# Zerocopter.net
KiCad netlist of a schematic drawn in EAGLE
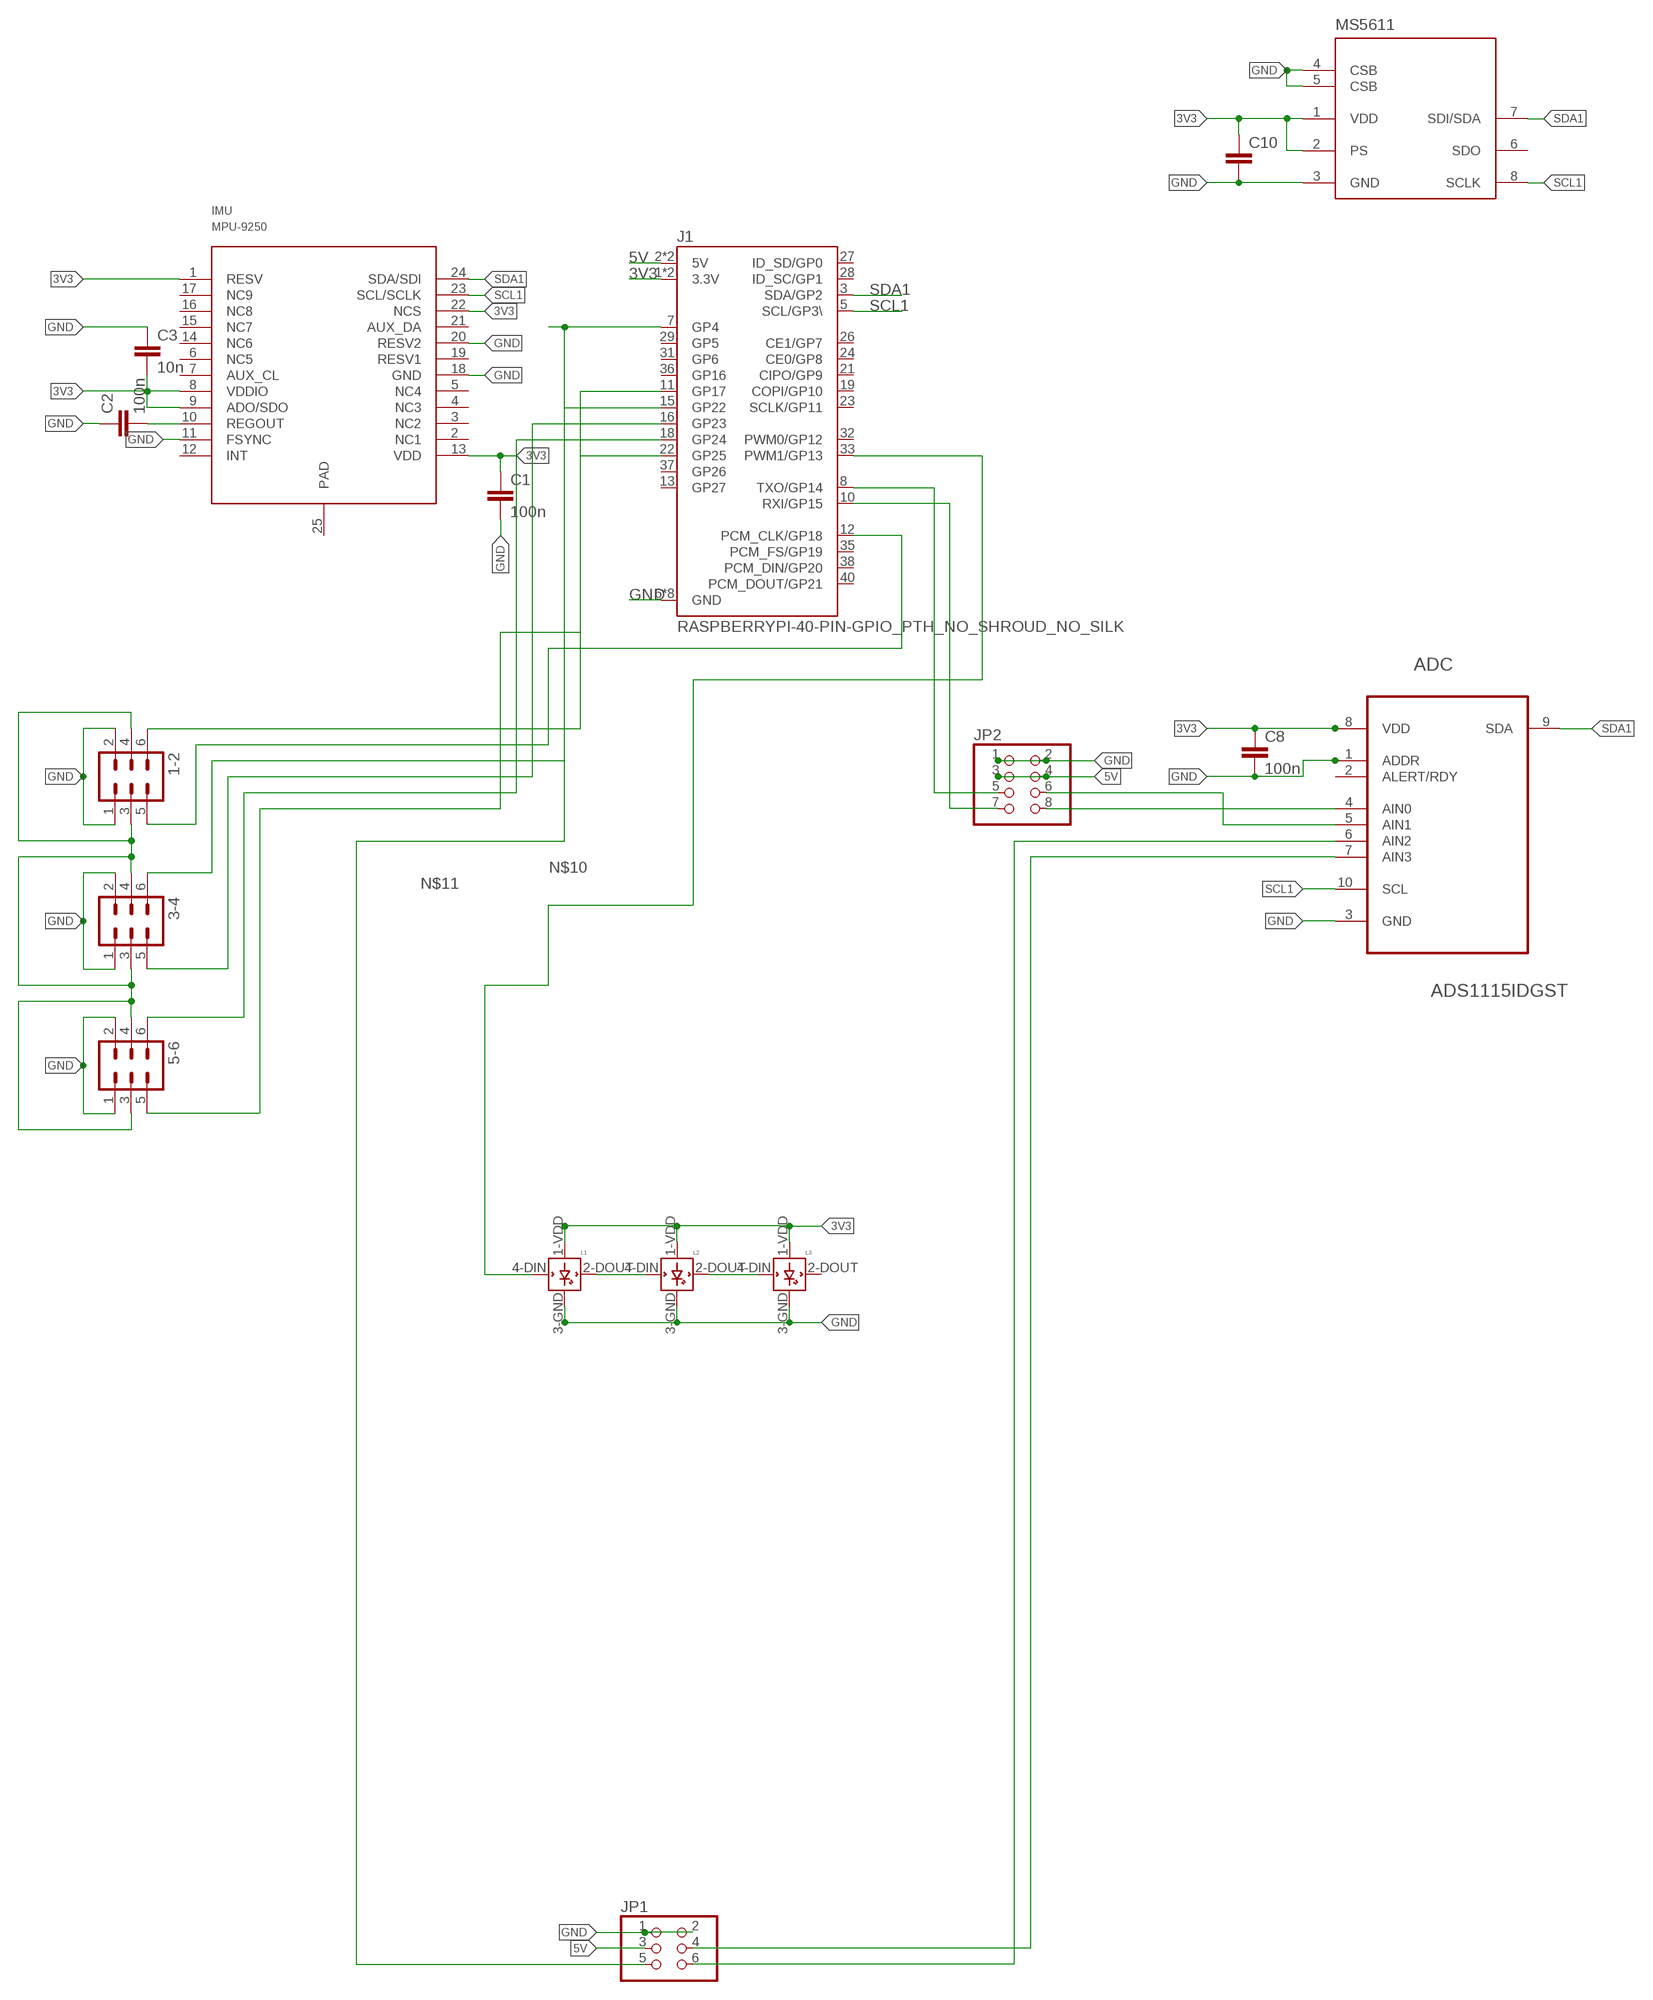
[diagram p0: schematic, sheet 1]

(export (version "E")
  (design (tool "Eeschema 10.0.6"))
  (components
    (comp (ref "1-2")
      (value "MA03-2")
      (footprint "eagle-import:MA03-2")
      (libsource (lib "eagle-import") (part "MA03-2"))
    )
    (comp (ref "3-4")
      (value "MA03-2")
      (footprint "eagle-import:MA03-2")
      (libsource (lib "eagle-import") (part "MA03-2"))
    )
    (comp (ref "5-6")
      (value "MA03-2")
      (footprint "eagle-import:MA03-2")
      (libsource (lib "eagle-import") (part "MA03-2"))
    )
    (comp (ref "ADC")
      (value "ADS1115IDGST")
      (footprint "eagle-import:SOP50P490X110-10N")
      (libsource (lib "eagle-import") (part "ADS1115IDGST"))
    )
    (comp (ref "C1")
      (value "100n")
      (footprint "eagle-import:C0603")
      (libsource (lib "eagle-import") (part "C-EUC0603"))
    )
    (comp (ref "C2")
      (value "100n")
      (footprint "eagle-import:C0603")
      (libsource (lib "eagle-import") (part "C-EUC0603"))
    )
    (comp (ref "C3")
      (value "10n")
      (footprint "eagle-import:C0603")
      (libsource (lib "eagle-import") (part "C-EUC0603"))
    )
    (comp (ref "C8")
      (value "100n")
      (footprint "eagle-import:C0603")
      (libsource (lib "eagle-import") (part "C-EUC0603"))
    )
    (comp (ref "C10")
      (value "C-EUC0603")
      (footprint "eagle-import:C0603")
      (libsource (lib "eagle-import") (part "C-EUC0603"))
    )
    (comp (ref "IMU")
      (value "MPU-9250")
      (footprint "eagle-import:LEAD-QFN24")
      (libsource (lib "eagle-import") (part "MPU-9250"))
    )
    (comp (ref "J1")
      (value "RASPBERRYPI-40-PIN-GPIO_PTH_NO_SHROUD_NO_SILK")
      (footprint "eagle-import:2X20_NOSILK")
      (libsource (lib "eagle-import") (part "RASPBERRYPI-40-PIN-GPIO_PTH_NO_SHROUD_NO_SILK"))
    )
    (comp (ref "JP1")
      (value "PINHD-2X3")
      (footprint "eagle-import:2X03")
      (libsource (lib "eagle-import") (part "PINHD-2X3"))
    )
    (comp (ref "JP2")
      (value "PINHD-2X4")
      (footprint "eagle-import:2X04")
      (libsource (lib "eagle-import") (part "PINHD-2X4"))
    )
    (comp (ref "L1")
      (value "WS2812B")
      (footprint "eagle-import:WS2812B")
      (libsource (lib "eagle-import") (part "WS2812B"))
    )
    (comp (ref "L2")
      (value "WS2812B")
      (footprint "eagle-import:WS2812B")
      (libsource (lib "eagle-import") (part "WS2812B"))
    )
    (comp (ref "L3")
      (value "WS2812B")
      (footprint "eagle-import:WS2812B")
      (libsource (lib "eagle-import") (part "WS2812B"))
    )
    (comp (ref "MS5611")
      (value "MS5611-01BA03")
      (footprint "eagle-import:SON125P300X500X100-8N")
      (libsource (lib "eagle-import") (part "MS5611-01BA03"))
    )
  )
  (nets
    (net (code "1") (name "/N$10") (class "Default")
      (node (ref "J1") (pin "33") (pinfunction "PWM1/GP13_33") (pintype "bidirectional"))
      (node (ref "L1") (pin "4-DIN") (pinfunction "DIN_4-DIN") (pintype "input"))
    )
    (net (code "2") (name "/N$11") (class "Default")
      (node (ref "J1") (pin "7") (pinfunction "GP4_7") (pintype "bidirectional"))
      (node (ref "JP1") (pin "5") (pinfunction "5_5") (pintype "passive"))
    )
    (net (code "3") (name "3V3") (class "Default")
      (node (ref "ADC") (pin "8") (pinfunction "VDD_8") (pintype "power_in"))
      (node (ref "C1") (pin "1") (pinfunction "1_1") (pintype "passive"))
      (node (ref "C10") (pin "1") (pinfunction "1_1") (pintype "passive"))
      (node (ref "C3") (pin "2") (pinfunction "2_2") (pintype "passive"))
      (node (ref "C8") (pin "1") (pinfunction "1_1") (pintype "passive"))
      (node (ref "IMU") (pin "1") (pinfunction "RESV_1") (pintype "bidirectional"))
      (node (ref "IMU") (pin "13") (pinfunction "VDD_13") (pintype "bidirectional"))
      (node (ref "IMU") (pin "22") (pinfunction "NCS_22") (pintype "bidirectional"))
      (node (ref "IMU") (pin "8") (pinfunction "VDDIO_8") (pintype "bidirectional"))
      (node (ref "IMU") (pin "9") (pinfunction "ADO/SDO_9") (pintype "bidirectional"))
      (node (ref "J1") (pin "1") (pinfunction "3.3V_1") (pintype "power_in"))
      (node (ref "J1") (pin "17") (pinfunction "3.3V_17") (pintype "power_in"))
      (node (ref "L1") (pin "1-VDD") (pinfunction "VDD_1-VDD") (pintype "bidirectional"))
      (node (ref "L2") (pin "1-VDD") (pinfunction "VDD_1-VDD") (pintype "bidirectional"))
      (node (ref "L3") (pin "1-VDD") (pinfunction "VDD_1-VDD") (pintype "bidirectional"))
      (node (ref "MS5611") (pin "1") (pinfunction "VDD_1") (pintype "power_in"))
      (node (ref "MS5611") (pin "2") (pinfunction "PS_2") (pintype "input"))
    )
    (net (code "4") (name "5V") (class "Default")
      (node (ref "J1") (pin "2") (pinfunction "5V_2") (pintype "power_in"))
      (node (ref "J1") (pin "4") (pinfunction "5V_4") (pintype "power_in"))
      (node (ref "JP1") (pin "3") (pinfunction "3_3") (pintype "passive"))
      (node (ref "JP2") (pin "3") (pinfunction "3_3") (pintype "passive"))
      (node (ref "JP2") (pin "4") (pinfunction "4_4") (pintype "passive"))
    )
    (net (code "5") (name "GND") (class "Default")
      (node (ref "1-2") (pin "1") (pinfunction "1_1") (pintype "passive"))
      (node (ref "1-2") (pin "2") (pinfunction "2_2") (pintype "passive"))
      (node (ref "3-4") (pin "1") (pinfunction "1_1") (pintype "passive"))
      (node (ref "3-4") (pin "2") (pinfunction "2_2") (pintype "passive"))
      (node (ref "5-6") (pin "1") (pinfunction "1_1") (pintype "passive"))
      (node (ref "5-6") (pin "2") (pinfunction "2_2") (pintype "passive"))
      (node (ref "ADC") (pin "1") (pinfunction "ADDR_1") (pintype "input"))
      (node (ref "ADC") (pin "3") (pinfunction "GND_3") (pintype "passive"))
      (node (ref "C1") (pin "2") (pinfunction "2_2") (pintype "passive"))
      (node (ref "C10") (pin "2") (pinfunction "2_2") (pintype "passive"))
      (node (ref "C2") (pin "1") (pinfunction "1_1") (pintype "passive"))
      (node (ref "C3") (pin "1") (pinfunction "1_1") (pintype "passive"))
      (node (ref "C8") (pin "2") (pinfunction "2_2") (pintype "passive"))
      (node (ref "IMU") (pin "11") (pinfunction "FSYNC_11") (pintype "bidirectional"))
      (node (ref "IMU") (pin "18") (pinfunction "GND_18") (pintype "bidirectional"))
      (node (ref "IMU") (pin "20") (pinfunction "RESV2_20") (pintype "bidirectional"))
      (node (ref "J1") (pin "14") (pinfunction "GND_14") (pintype "power_in"))
      (node (ref "J1") (pin "20") (pinfunction "GND_20") (pintype "power_in"))
      (node (ref "J1") (pin "25") (pinfunction "GND_25") (pintype "power_in"))
      (node (ref "J1") (pin "30") (pinfunction "GND_30") (pintype "power_in"))
      (node (ref "J1") (pin "34") (pinfunction "GND_34") (pintype "power_in"))
      (node (ref "J1") (pin "39") (pinfunction "GND_39") (pintype "power_in"))
      (node (ref "J1") (pin "6") (pinfunction "GND_6") (pintype "power_in"))
      (node (ref "J1") (pin "9") (pinfunction "GND_9") (pintype "power_in"))
      (node (ref "JP1") (pin "1") (pinfunction "1_1") (pintype "passive"))
      (node (ref "JP1") (pin "2") (pinfunction "2_2") (pintype "passive"))
      (node (ref "JP2") (pin "1") (pinfunction "1_1") (pintype "passive"))
      (node (ref "JP2") (pin "2") (pinfunction "2_2") (pintype "passive"))
      (node (ref "L1") (pin "3-GND") (pinfunction "GND_3-GND") (pintype "bidirectional"))
      (node (ref "L2") (pin "3-GND") (pinfunction "GND_3-GND") (pintype "bidirectional"))
      (node (ref "L3") (pin "3-GND") (pinfunction "GND_3-GND") (pintype "bidirectional"))
      (node (ref "MS5611") (pin "3") (pinfunction "GND_3") (pintype "power_in"))
      (node (ref "MS5611") (pin "4") (pinfunction "CSB_4") (pintype "input"))
      (node (ref "MS5611") (pin "5") (pinfunction "CSB_5") (pintype "input"))
    )
    (net (code "6") (name "Net-(1-2-Pad3)") (class "Default")
      (node (ref "1-2") (pin "3") (pinfunction "3_3") (pintype "passive"))
      (node (ref "1-2") (pin "4") (pinfunction "4_4") (pintype "passive"))
      (node (ref "3-4") (pin "3") (pinfunction "3_3") (pintype "passive"))
      (node (ref "3-4") (pin "4") (pinfunction "4_4") (pintype "passive"))
      (node (ref "5-6") (pin "3") (pinfunction "3_3") (pintype "passive"))
      (node (ref "5-6") (pin "4") (pinfunction "4_4") (pintype "passive"))
    )
    (net (code "7") (name "Net-(ADC-AIN0)") (class "Default")
      (node (ref "ADC") (pin "4") (pinfunction "AIN0_4") (pintype "input"))
      (node (ref "JP2") (pin "8") (pinfunction "8_8") (pintype "passive"))
    )
    (net (code "8") (name "Net-(ADC-AIN1)") (class "Default")
      (node (ref "ADC") (pin "5") (pinfunction "AIN1_5") (pintype "input"))
      (node (ref "JP2") (pin "6") (pinfunction "6_6") (pintype "passive"))
    )
    (net (code "9") (name "Net-(ADC-AIN2)") (class "Default")
      (node (ref "ADC") (pin "6") (pinfunction "AIN2_6") (pintype "input"))
      (node (ref "JP1") (pin "6") (pinfunction "6_6") (pintype "passive"))
    )
    (net (code "10") (name "Net-(ADC-AIN3)") (class "Default")
      (node (ref "ADC") (pin "7") (pinfunction "AIN3_7") (pintype "input"))
      (node (ref "JP1") (pin "4") (pinfunction "4_4") (pintype "passive"))
    )
    (net (code "11") (name "Net-(IMU-REGOUT)") (class "Default")
      (node (ref "C2") (pin "2") (pinfunction "2_2") (pintype "passive"))
      (node (ref "IMU") (pin "10") (pinfunction "REGOUT_10") (pintype "bidirectional"))
    )
    (net (code "12") (name "Net-(J1-GP17)") (class "Default")
      (node (ref "1-2") (pin "6") (pinfunction "6_6") (pintype "passive"))
      (node (ref "J1") (pin "11") (pinfunction "GP17_11") (pintype "bidirectional"))
    )
    (net (code "13") (name "Net-(J1-GP22)") (class "Default")
      (node (ref "3-4") (pin "6") (pinfunction "6_6") (pintype "passive"))
      (node (ref "J1") (pin "15") (pinfunction "GP22_15") (pintype "bidirectional"))
    )
    (net (code "14") (name "Net-(J1-GP23)") (class "Default")
      (node (ref "3-4") (pin "5") (pinfunction "5_5") (pintype "passive"))
      (node (ref "J1") (pin "16") (pinfunction "GP23_16") (pintype "bidirectional"))
    )
    (net (code "15") (name "Net-(J1-GP24)") (class "Default")
      (node (ref "5-6") (pin "6") (pinfunction "6_6") (pintype "passive"))
      (node (ref "J1") (pin "18") (pinfunction "GP24_18") (pintype "bidirectional"))
    )
    (net (code "16") (name "Net-(J1-GP25)") (class "Default")
      (node (ref "5-6") (pin "5") (pinfunction "5_5") (pintype "passive"))
      (node (ref "J1") (pin "22") (pinfunction "GP25_22") (pintype "bidirectional"))
    )
    (net (code "17") (name "Net-(J1-PCM_CLK{slash}GP18)") (class "Default")
      (node (ref "1-2") (pin "5") (pinfunction "5_5") (pintype "passive"))
      (node (ref "J1") (pin "12") (pinfunction "PCM_CLK/GP18_12") (pintype "bidirectional"))
    )
    (net (code "18") (name "Net-(J1-RXI{slash}GP15)") (class "Default")
      (node (ref "J1") (pin "10") (pinfunction "RXI/GP15_10") (pintype "input"))
      (node (ref "JP2") (pin "7") (pinfunction "7_7") (pintype "passive"))
    )
    (net (code "19") (name "Net-(J1-TXO{slash}GP14)") (class "Default")
      (node (ref "J1") (pin "8") (pinfunction "TXO/GP14_8") (pintype "output"))
      (node (ref "JP2") (pin "5") (pinfunction "5_5") (pintype "passive"))
    )
    (net (code "20") (name "Net-(L1-DOUT)") (class "Default")
      (node (ref "L1") (pin "2-DOUT") (pinfunction "DOUT_2-DOUT") (pintype "output"))
      (node (ref "L2") (pin "4-DIN") (pinfunction "DIN_4-DIN") (pintype "input"))
    )
    (net (code "21") (name "Net-(L2-DOUT)") (class "Default")
      (node (ref "L2") (pin "2-DOUT") (pinfunction "DOUT_2-DOUT") (pintype "output"))
      (node (ref "L3") (pin "4-DIN") (pinfunction "DIN_4-DIN") (pintype "input"))
    )
    (net (code "22") (name "SCL1") (class "Default")
      (node (ref "ADC") (pin "10") (pinfunction "SCL_10") (pintype "input"))
      (node (ref "IMU") (pin "23") (pinfunction "SCL/SCLK_23") (pintype "bidirectional"))
      (node (ref "J1") (pin "5") (pinfunction "SCL/GP3\\_5") (pintype "bidirectional"))
      (node (ref "MS5611") (pin "8") (pinfunction "SCLK_8") (pintype "input"))
    )
    (net (code "23") (name "SDA1") (class "Default")
      (node (ref "ADC") (pin "9") (pinfunction "SDA_9") (pintype "bidirectional"))
      (node (ref "IMU") (pin "24") (pinfunction "SDA/SDI_24") (pintype "bidirectional"))
      (node (ref "J1") (pin "3") (pinfunction "SDA/GP2_3") (pintype "bidirectional"))
      (node (ref "MS5611") (pin "7") (pinfunction "SDI/SDA_7") (pintype "bidirectional"))
    )
    (net (code "24") (name "unconnected-(ADC-ALERT{slash}RDY-Pad2)") (class "Default")
      (node (ref "ADC") (pin "2") (pinfunction "ALERT/RDY_2") (pintype "input"))
    )
    (net (code "25") (name "unconnected-(IMU-AUX_CL-Pad7)") (class "Default")
      (node (ref "IMU") (pin "7") (pinfunction "AUX_CL_7") (pintype "bidirectional"))
    )
    (net (code "26") (name "unconnected-(IMU-AUX_DA-Pad21)") (class "Default")
      (node (ref "IMU") (pin "21") (pinfunction "AUX_DA_21") (pintype "bidirectional"))
    )
    (net (code "27") (name "unconnected-(IMU-INT-Pad12)") (class "Default")
      (node (ref "IMU") (pin "12") (pinfunction "INT_12") (pintype "bidirectional"))
    )
    (net (code "28") (name "unconnected-(IMU-NC1-Pad2)") (class "Default")
      (node (ref "IMU") (pin "2") (pinfunction "NC1_2") (pintype "bidirectional"))
    )
    (net (code "29") (name "unconnected-(IMU-NC2-Pad3)") (class "Default")
      (node (ref "IMU") (pin "3") (pinfunction "NC2_3") (pintype "bidirectional"))
    )
    (net (code "30") (name "unconnected-(IMU-NC3-Pad4)") (class "Default")
      (node (ref "IMU") (pin "4") (pinfunction "NC3_4") (pintype "bidirectional"))
    )
    (net (code "31") (name "unconnected-(IMU-NC4-Pad5)") (class "Default")
      (node (ref "IMU") (pin "5") (pinfunction "NC4_5") (pintype "bidirectional"))
    )
    (net (code "32") (name "unconnected-(IMU-NC5-Pad6)") (class "Default")
      (node (ref "IMU") (pin "6") (pinfunction "NC5_6") (pintype "bidirectional"))
    )
    (net (code "33") (name "unconnected-(IMU-NC6-Pad14)") (class "Default")
      (node (ref "IMU") (pin "14") (pinfunction "NC6_14") (pintype "bidirectional"))
    )
    (net (code "34") (name "unconnected-(IMU-NC7-Pad15)") (class "Default")
      (node (ref "IMU") (pin "15") (pinfunction "NC7_15") (pintype "bidirectional"))
    )
    (net (code "35") (name "unconnected-(IMU-NC8-Pad16)") (class "Default")
      (node (ref "IMU") (pin "16") (pinfunction "NC8_16") (pintype "bidirectional"))
    )
    (net (code "36") (name "unconnected-(IMU-NC9-Pad17)") (class "Default")
      (node (ref "IMU") (pin "17") (pinfunction "NC9_17") (pintype "bidirectional"))
    )
    (net (code "37") (name "unconnected-(IMU-PAD-Pad25)") (class "Default")
      (node (ref "IMU") (pin "25") (pinfunction "PAD_25") (pintype "bidirectional"))
    )
    (net (code "38") (name "unconnected-(IMU-RESV1-Pad19)") (class "Default")
      (node (ref "IMU") (pin "19") (pinfunction "RESV1_19") (pintype "bidirectional"))
    )
    (net (code "39") (name "unconnected-(J1-CE0{slash}GP8-Pad24)") (class "Default")
      (node (ref "J1") (pin "24") (pinfunction "CE0/GP8_24") (pintype "output"))
    )
    (net (code "40") (name "unconnected-(J1-CE1{slash}GP7-Pad26)") (class "Default")
      (node (ref "J1") (pin "26") (pinfunction "CE1/GP7_26") (pintype "output"))
    )
    (net (code "41") (name "unconnected-(J1-CIPO{slash}GP9-Pad21)") (class "Default")
      (node (ref "J1") (pin "21") (pinfunction "CIPO/GP9_21") (pintype "input"))
    )
    (net (code "42") (name "unconnected-(J1-COPI{slash}GP10-Pad19)") (class "Default")
      (node (ref "J1") (pin "19") (pinfunction "COPI/GP10_19") (pintype "output"))
    )
    (net (code "43") (name "unconnected-(J1-GP5-Pad29)") (class "Default")
      (node (ref "J1") (pin "29") (pinfunction "GP5_29") (pintype "bidirectional"))
    )
    (net (code "44") (name "unconnected-(J1-GP6-Pad31)") (class "Default")
      (node (ref "J1") (pin "31") (pinfunction "GP6_31") (pintype "bidirectional"))
    )
    (net (code "45") (name "unconnected-(J1-GP16-Pad36)") (class "Default")
      (node (ref "J1") (pin "36") (pinfunction "GP16_36") (pintype "bidirectional"))
    )
    (net (code "46") (name "unconnected-(J1-GP26-Pad37)") (class "Default")
      (node (ref "J1") (pin "37") (pinfunction "GP26_37") (pintype "bidirectional"))
    )
    (net (code "47") (name "unconnected-(J1-GP27-Pad13)") (class "Default")
      (node (ref "J1") (pin "13") (pinfunction "GP27_13") (pintype "bidirectional"))
    )
    (net (code "48") (name "unconnected-(J1-ID_SC{slash}GP1-Pad28)") (class "Default")
      (node (ref "J1") (pin "28") (pinfunction "ID_SC/GP1_28") (pintype "bidirectional"))
    )
    (net (code "49") (name "unconnected-(J1-ID_SD{slash}GP0-Pad27)") (class "Default")
      (node (ref "J1") (pin "27") (pinfunction "ID_SD/GP0_27") (pintype "bidirectional"))
    )
    (net (code "50") (name "unconnected-(J1-PCM_DIN{slash}GP20-Pad38)") (class "Default")
      (node (ref "J1") (pin "38") (pinfunction "PCM_DIN/GP20_38") (pintype "bidirectional"))
    )
    (net (code "51") (name "unconnected-(J1-PCM_DOUT{slash}GP21-Pad40)") (class "Default")
      (node (ref "J1") (pin "40") (pinfunction "PCM_DOUT/GP21_40") (pintype "bidirectional"))
    )
    (net (code "52") (name "unconnected-(J1-PCM_FS{slash}GP19-Pad35)") (class "Default")
      (node (ref "J1") (pin "35") (pinfunction "PCM_FS/GP19_35") (pintype "bidirectional"))
    )
    (net (code "53") (name "unconnected-(J1-PWM0{slash}GP12-Pad32)") (class "Default")
      (node (ref "J1") (pin "32") (pinfunction "PWM0/GP12_32") (pintype "bidirectional"))
    )
    (net (code "54") (name "unconnected-(J1-SCLK{slash}GP11-Pad23)") (class "Default")
      (node (ref "J1") (pin "23") (pinfunction "SCLK/GP11_23") (pintype "output"))
    )
    (net (code "55") (name "unconnected-(L3-DOUT-Pad2-DOUT)") (class "Default")
      (node (ref "L3") (pin "2-DOUT") (pinfunction "DOUT_2-DOUT") (pintype "output"))
    )
    (net (code "56") (name "unconnected-(MS5611-SDO-Pad6)") (class "Default")
      (node (ref "MS5611") (pin "6") (pinfunction "SDO_6") (pintype "output"))
    )
  )
)
